# DOut.net
KiCad netlist of a schematic drawn in Altium Designer
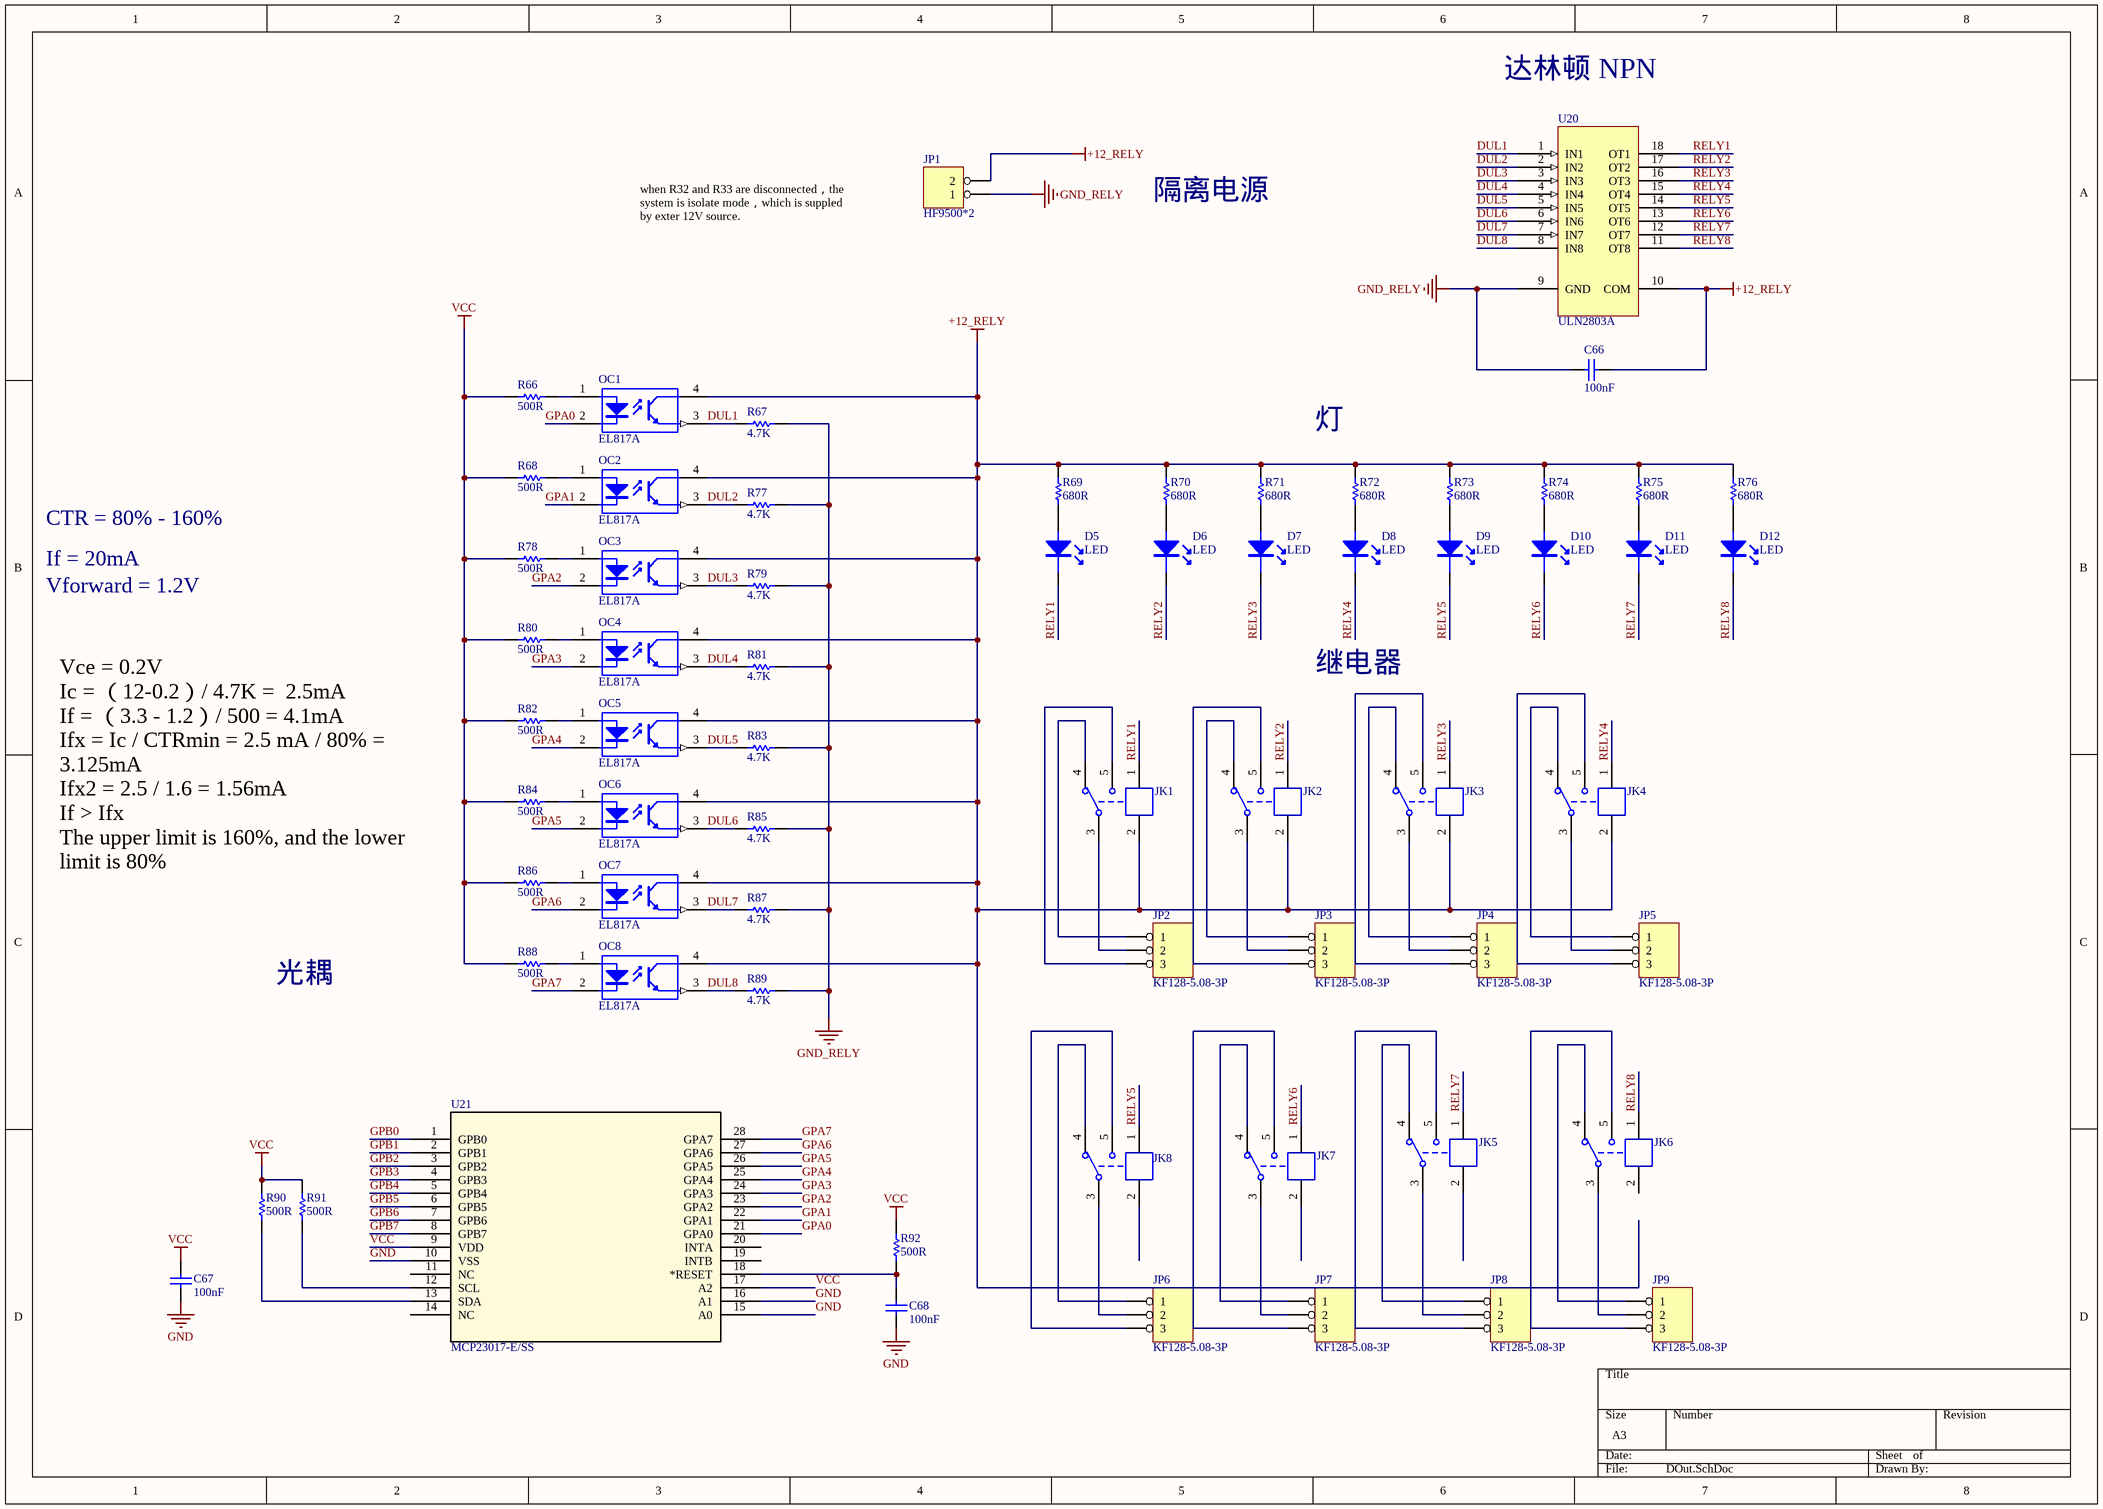
[diagram p0: DOut.SchDoc]

(export (version "E")
  (design (tool "Eeschema 10.0.6"))
  (components
    (comp (ref "C66")
      (value "100nF")
      (footprint "0603C")
      (description "Capacitor")
      (fields (field (name "PUBLISHER") "Altium Limited"))
      (libsource (lib "LJTV1.0") (part "CAP"))
    )
    (comp (ref "C67")
      (value "100nF")
      (footprint "0603C")
      (description "Capacitor")
      (fields (field (name "PUBLISHER") "Altium Limited"))
      (libsource (lib "WarShip_ExtraBoard") (part "CAP"))
    )
    (comp (ref "C68")
      (value "100nF")
      (footprint "0603C")
      (description "Capacitor")
      (fields (field (name "PUBLISHER") "Altium Limited"))
      (libsource (lib "WarShip_ExtraBoard") (part "CAP"))
    )
    (comp (ref "D5")
      (value "LED")
      (footprint "LED-0603G")
      (description "LED 发光二极管")
      (libsource (lib "LJTV1.0") (part "LED"))
    )
    (comp (ref "D6")
      (value "LED")
      (footprint "LED-0603G")
      (description "LED 发光二极管")
      (libsource (lib "LJTV1.0") (part "LED"))
    )
    (comp (ref "D7")
      (value "LED")
      (footprint "LED-0603G")
      (description "LED 发光二极管")
      (libsource (lib "LJTV1.0") (part "LED"))
    )
    (comp (ref "D8")
      (value "LED")
      (footprint "LED-0603G")
      (description "LED 发光二极管")
      (libsource (lib "LJTV1.0") (part "LED"))
    )
    (comp (ref "D9")
      (value "LED")
      (footprint "LED-0603G")
      (description "LED 发光二极管")
      (libsource (lib "LJTV1.0") (part "LED"))
    )
    (comp (ref "D10")
      (value "LED")
      (footprint "LED-0603G")
      (description "LED 发光二极管")
      (libsource (lib "LJTV1.0") (part "LED"))
    )
    (comp (ref "D11")
      (value "LED")
      (footprint "LED-0603G")
      (description "LED 发光二极管")
      (libsource (lib "LJTV1.0") (part "LED"))
    )
    (comp (ref "D12")
      (value "LED")
      (footprint "LED-0603G")
      (description "LED 发光二极管")
      (libsource (lib "LJTV1.0") (part "LED"))
    )
    (comp (ref "JK1")
      (value "SRD-05VDC-SL-C")
      (footprint "SRD-C_B")
      (description "5V一组转换")
      (libsource (lib "LJTV1.0") (part "SRD-05VDC-SL-C"))
    )
    (comp (ref "JK2")
      (value "SRD-05VDC-SL-C")
      (footprint "SRD-C_B")
      (description "5V一组转换")
      (libsource (lib "LJTV1.0") (part "SRD-05VDC-SL-C"))
    )
    (comp (ref "JK3")
      (value "SRD-05VDC-SL-C")
      (footprint "SRD-C_B")
      (description "5V一组转换")
      (libsource (lib "LJTV1.0") (part "SRD-05VDC-SL-C"))
    )
    (comp (ref "JK4")
      (value "SRD-05VDC-SL-C")
      (footprint "SRD-C_B")
      (description "5V一组转换")
      (libsource (lib "LJTV1.0") (part "SRD-05VDC-SL-C"))
    )
    (comp (ref "JK5")
      (value "SRD-05VDC-SL-C")
      (footprint "SRD-C_B")
      (description "5V一组转换")
      (libsource (lib "LJTV1.0") (part "SRD-05VDC-SL-C"))
    )
    (comp (ref "JK6")
      (value "SRD-05VDC-SL-C")
      (footprint "SRD-C_B")
      (description "5V一组转换")
      (libsource (lib "LJTV1.0") (part "SRD-05VDC-SL-C"))
    )
    (comp (ref "JK7")
      (value "SRD-05VDC-SL-C")
      (footprint "SRD-C_B")
      (description "5V一组转换")
      (libsource (lib "LJTV1.0") (part "SRD-05VDC-SL-C"))
    )
    (comp (ref "JK8")
      (value "SRD-05VDC-SL-C")
      (footprint "SRD-C_B")
      (description "5V一组转换")
      (libsource (lib "LJTV1.0") (part "SRD-05VDC-SL-C"))
    )
    (comp (ref "JP1")
      (value "HF9500*2")
      (footprint "KF128-5.08-2P")
      (libsource (lib "LJTV1.0") (part "HEADER 2"))
    )
    (comp (ref "JP2")
      (value "KF128-5.08-3P")
      (footprint "KF128-5.08-3P")
      (libsource (lib "LJTV1.0") (part "HEADER 3"))
    )
    (comp (ref "JP3")
      (value "KF128-5.08-3P")
      (footprint "KF128-5.08-3P")
      (libsource (lib "LJTV1.0") (part "HEADER 3"))
    )
    (comp (ref "JP4")
      (value "KF128-5.08-3P")
      (footprint "KF128-5.08-3P")
      (libsource (lib "LJTV1.0") (part "HEADER 3"))
    )
    (comp (ref "JP5")
      (value "KF128-5.08-3P")
      (footprint "KF128-5.08-3P")
      (libsource (lib "LJTV1.0") (part "HEADER 3"))
    )
    (comp (ref "JP6")
      (value "KF128-5.08-3P")
      (footprint "KF128-5.08-3P")
      (libsource (lib "LJTV1.0") (part "HEADER 3"))
    )
    (comp (ref "JP7")
      (value "KF128-5.08-3P")
      (footprint "KF128-5.08-3P")
      (libsource (lib "LJTV1.0") (part "HEADER 3"))
    )
    (comp (ref "JP8")
      (value "KF128-5.08-3P")
      (footprint "KF128-5.08-3P")
      (libsource (lib "LJTV1.0") (part "HEADER 3"))
    )
    (comp (ref "JP9")
      (value "KF128-5.08-3P")
      (footprint "KF128-5.08-3P")
      (libsource (lib "LJTV1.0") (part "HEADER 3"))
    )
    (comp (ref "OC1")
      (value "EL817A")
      (footprint "SMD_PC817")
      (description "线性光耦")
      (libsource (lib "LJTV1.0") (part "EL357N"))
    )
    (comp (ref "OC2")
      (value "EL817A")
      (footprint "SMD_PC817")
      (description "线性光耦")
      (libsource (lib "LJTV1.0") (part "EL357N"))
    )
    (comp (ref "OC3")
      (value "EL817A")
      (footprint "SMD_PC817")
      (description "线性光耦")
      (libsource (lib "LJTV1.0") (part "EL357N"))
    )
    (comp (ref "OC4")
      (value "EL817A")
      (footprint "SMD_PC817")
      (description "线性光耦")
      (libsource (lib "LJTV1.0") (part "EL357N"))
    )
    (comp (ref "OC5")
      (value "EL817A")
      (footprint "SMD_PC817")
      (description "线性光耦")
      (libsource (lib "LJTV1.0") (part "EL357N"))
    )
    (comp (ref "OC6")
      (value "EL817A")
      (footprint "SMD_PC817")
      (description "线性光耦")
      (libsource (lib "LJTV1.0") (part "EL357N"))
    )
    (comp (ref "OC7")
      (value "EL817A")
      (footprint "SMD_PC817")
      (description "线性光耦")
      (libsource (lib "LJTV1.0") (part "EL357N"))
    )
    (comp (ref "OC8")
      (value "EL817A")
      (footprint "SMD_PC817")
      (description "线性光耦")
      (libsource (lib "LJTV1.0") (part "EL357N"))
    )
    (comp (ref "R66")
      (value "500R")
      (footprint "0805R")
      (description "Resistor")
      (fields (field (name "PUBLISHER") "Altium Limited"))
      (libsource (lib "LJTV1.0") (part "RES"))
    )
    (comp (ref "R67")
      (value "4.7K")
      (footprint "0603R")
      (description "Resistor")
      (fields (field (name "PUBLISHER") "Altium Limited"))
      (libsource (lib "LJTV1.0") (part "RES"))
    )
    (comp (ref "R68")
      (value "500R")
      (footprint "0805R")
      (description "Resistor")
      (fields (field (name "PUBLISHER") "Altium Limited"))
      (libsource (lib "LJTV1.0") (part "RES"))
    )
    (comp (ref "R69")
      (value "680R")
      (footprint "0805R")
      (description "Resistor")
      (fields (field (name "PUBLISHER") "Altium Limited"))
      (libsource (lib "LJTV1.0") (part "RES"))
    )
    (comp (ref "R70")
      (value "680R")
      (footprint "0805R")
      (description "Resistor")
      (fields (field (name "PUBLISHER") "Altium Limited"))
      (libsource (lib "LJTV1.0") (part "RES"))
    )
    (comp (ref "R71")
      (value "680R")
      (footprint "0805R")
      (description "Resistor")
      (fields (field (name "PUBLISHER") "Altium Limited"))
      (libsource (lib "LJTV1.0") (part "RES"))
    )
    (comp (ref "R72")
      (value "680R")
      (footprint "0805R")
      (description "Resistor")
      (fields (field (name "PUBLISHER") "Altium Limited"))
      (libsource (lib "LJTV1.0") (part "RES"))
    )
    (comp (ref "R73")
      (value "680R")
      (footprint "0805R")
      (description "Resistor")
      (fields (field (name "PUBLISHER") "Altium Limited"))
      (libsource (lib "LJTV1.0") (part "RES"))
    )
    (comp (ref "R74")
      (value "680R")
      (footprint "0805R")
      (description "Resistor")
      (fields (field (name "PUBLISHER") "Altium Limited"))
      (libsource (lib "LJTV1.0") (part "RES"))
    )
    (comp (ref "R75")
      (value "680R")
      (footprint "0805R")
      (description "Resistor")
      (fields (field (name "PUBLISHER") "Altium Limited"))
      (libsource (lib "LJTV1.0") (part "RES"))
    )
    (comp (ref "R76")
      (value "680R")
      (footprint "0805R")
      (description "Resistor")
      (fields (field (name "PUBLISHER") "Altium Limited"))
      (libsource (lib "LJTV1.0") (part "RES"))
    )
    (comp (ref "R77")
      (value "4.7K")
      (footprint "0603R")
      (description "Resistor")
      (fields (field (name "PUBLISHER") "Altium Limited"))
      (libsource (lib "LJTV1.0") (part "RES"))
    )
    (comp (ref "R78")
      (value "500R")
      (footprint "0805R")
      (description "Resistor")
      (fields (field (name "PUBLISHER") "Altium Limited"))
      (libsource (lib "LJTV1.0") (part "RES"))
    )
    (comp (ref "R79")
      (value "4.7K")
      (footprint "0603R")
      (description "Resistor")
      (fields (field (name "PUBLISHER") "Altium Limited"))
      (libsource (lib "LJTV1.0") (part "RES"))
    )
    (comp (ref "R80")
      (value "500R")
      (footprint "0805R")
      (description "Resistor")
      (fields (field (name "PUBLISHER") "Altium Limited"))
      (libsource (lib "LJTV1.0") (part "RES"))
    )
    (comp (ref "R81")
      (value "4.7K")
      (footprint "0603R")
      (description "Resistor")
      (fields (field (name "PUBLISHER") "Altium Limited"))
      (libsource (lib "LJTV1.0") (part "RES"))
    )
    (comp (ref "R82")
      (value "500R")
      (footprint "0805R")
      (description "Resistor")
      (fields (field (name "PUBLISHER") "Altium Limited"))
      (libsource (lib "LJTV1.0") (part "RES"))
    )
    (comp (ref "R83")
      (value "4.7K")
      (footprint "0603R")
      (description "Resistor")
      (fields (field (name "PUBLISHER") "Altium Limited"))
      (libsource (lib "LJTV1.0") (part "RES"))
    )
    (comp (ref "R84")
      (value "500R")
      (footprint "0805R")
      (description "Resistor")
      (fields (field (name "PUBLISHER") "Altium Limited"))
      (libsource (lib "LJTV1.0") (part "RES"))
    )
    (comp (ref "R85")
      (value "4.7K")
      (footprint "0603R")
      (description "Resistor")
      (fields (field (name "PUBLISHER") "Altium Limited"))
      (libsource (lib "LJTV1.0") (part "RES"))
    )
    (comp (ref "R86")
      (value "500R")
      (footprint "0805R")
      (description "Resistor")
      (fields (field (name "PUBLISHER") "Altium Limited"))
      (libsource (lib "LJTV1.0") (part "RES"))
    )
    (comp (ref "R87")
      (value "4.7K")
      (footprint "0603R")
      (description "Resistor")
      (fields (field (name "PUBLISHER") "Altium Limited"))
      (libsource (lib "LJTV1.0") (part "RES"))
    )
    (comp (ref "R88")
      (value "500R")
      (footprint "0805R")
      (description "Resistor")
      (fields (field (name "PUBLISHER") "Altium Limited"))
      (libsource (lib "LJTV1.0") (part "RES"))
    )
    (comp (ref "R89")
      (value "4.7K")
      (footprint "0603R")
      (description "Resistor")
      (fields (field (name "PUBLISHER") "Altium Limited"))
      (libsource (lib "LJTV1.0") (part "RES"))
    )
    (comp (ref "R90")
      (value "500R")
      (footprint "0805R")
      (description "Resistor")
      (fields (field (name "PUBLISHER") "Altium Limited"))
      (libsource (lib "WarShip_ExtraBoard") (part "RES"))
    )
    (comp (ref "R91")
      (value "500R")
      (footprint "0805R")
      (description "Resistor")
      (fields (field (name "PUBLISHER") "Altium Limited"))
      (libsource (lib "WarShip_ExtraBoard") (part "RES"))
    )
    (comp (ref "R92")
      (value "500R")
      (footprint "0805R")
      (description "Resistor")
      (fields (field (name "PUBLISHER") "Altium Limited"))
      (libsource (lib "WarShip_ExtraBoard") (part "RES"))
    )
    (comp (ref "U20")
      (value "ULN2803A")
      (footprint "SOP18 - 300mil")
      (description "8 channels Darlington")
      (libsource (lib "LJTV1.0") (part "ULN2803A"))
    )
    (comp (ref "U21")
      (value "MCP23017-E/SS")
      (footprint "SSOP28_MC_MCH")
      (description "No Description Available")
      (fields (field (name "COPYRIGHT") "Copyright (C) 2021 Ultra Librarian. All rights reserved."))
      (libsource (lib "MCP23017-E&slash_SS") (part "MCP23017-E/SS"))
    )
  )
  (nets
    (net (code "1") (name "+12_RELY") (class "Default")
      (node (ref "C66") (pin "2") (pinfunction "2_2") (pintype "passive"))
      (node (ref "JK1") (pin "2") (pinfunction "2_2") (pintype "passive"))
      (node (ref "JK2") (pin "2") (pinfunction "2_2") (pintype "passive"))
      (node (ref "JK3") (pin "2") (pinfunction "2_2") (pintype "passive"))
      (node (ref "JK4") (pin "2") (pinfunction "2_2") (pintype "passive"))
      (node (ref "JP1") (pin "2") (pinfunction "2_2") (pintype "passive"))
      (node (ref "OC1") (pin "4") (pinfunction "C_4") (pintype "passive"))
      (node (ref "OC2") (pin "4") (pinfunction "C_4") (pintype "passive"))
      (node (ref "OC3") (pin "4") (pinfunction "C_4") (pintype "passive"))
      (node (ref "OC4") (pin "4") (pinfunction "C_4") (pintype "passive"))
      (node (ref "OC5") (pin "4") (pinfunction "C_4") (pintype "passive"))
      (node (ref "OC6") (pin "4") (pinfunction "C_4") (pintype "passive"))
      (node (ref "OC7") (pin "4") (pinfunction "C_4") (pintype "passive"))
      (node (ref "OC8") (pin "4") (pinfunction "C_4") (pintype "passive"))
      (node (ref "R69") (pin "1") (pinfunction "1_1") (pintype "passive"))
      (node (ref "R70") (pin "1") (pinfunction "1_1") (pintype "passive"))
      (node (ref "R71") (pin "1") (pinfunction "1_1") (pintype "passive"))
      (node (ref "R72") (pin "1") (pinfunction "1_1") (pintype "passive"))
      (node (ref "R73") (pin "1") (pinfunction "1_1") (pintype "passive"))
      (node (ref "R74") (pin "1") (pinfunction "1_1") (pintype "passive"))
      (node (ref "R75") (pin "1") (pinfunction "1_1") (pintype "passive"))
      (node (ref "R76") (pin "1") (pinfunction "1_1") (pintype "passive"))
      (node (ref "U20") (pin "10") (pinfunction "COM_10") (pintype "power_in"))
    )
    (net (code "2") (name "/DUL1") (class "Default")
      (node (ref "OC1") (pin "3") (pinfunction "E_3") (pintype "output"))
      (node (ref "R67") (pin "1") (pinfunction "1_1") (pintype "passive"))
      (node (ref "U20") (pin "1") (pinfunction "IN1_1") (pintype "input"))
    )
    (net (code "3") (name "/DUL2") (class "Default")
      (node (ref "OC2") (pin "3") (pinfunction "E_3") (pintype "output"))
      (node (ref "R77") (pin "1") (pinfunction "1_1") (pintype "passive"))
      (node (ref "U20") (pin "2") (pinfunction "IN2_2") (pintype "input"))
    )
    (net (code "4") (name "/DUL3") (class "Default")
      (node (ref "OC3") (pin "3") (pinfunction "E_3") (pintype "output"))
      (node (ref "R79") (pin "1") (pinfunction "1_1") (pintype "passive"))
      (node (ref "U20") (pin "3") (pinfunction "IN3_3") (pintype "input"))
    )
    (net (code "5") (name "/DUL4") (class "Default")
      (node (ref "OC4") (pin "3") (pinfunction "E_3") (pintype "output"))
      (node (ref "R81") (pin "1") (pinfunction "1_1") (pintype "passive"))
      (node (ref "U20") (pin "4") (pinfunction "IN4_4") (pintype "input"))
    )
    (net (code "6") (name "/DUL5") (class "Default")
      (node (ref "OC5") (pin "3") (pinfunction "E_3") (pintype "output"))
      (node (ref "R83") (pin "1") (pinfunction "1_1") (pintype "passive"))
      (node (ref "U20") (pin "5") (pinfunction "IN5_5") (pintype "input"))
    )
    (net (code "7") (name "/DUL6") (class "Default")
      (node (ref "OC6") (pin "3") (pinfunction "E_3") (pintype "output"))
      (node (ref "R85") (pin "1") (pinfunction "1_1") (pintype "passive"))
      (node (ref "U20") (pin "6") (pinfunction "IN6_6") (pintype "input"))
    )
    (net (code "8") (name "/DUL7") (class "Default")
      (node (ref "OC7") (pin "3") (pinfunction "E_3") (pintype "output"))
      (node (ref "R87") (pin "1") (pinfunction "1_1") (pintype "passive"))
      (node (ref "U20") (pin "7") (pinfunction "IN7_7") (pintype "input"))
    )
    (net (code "9") (name "/DUL8") (class "Default")
      (node (ref "OC8") (pin "3") (pinfunction "E_3") (pintype "output"))
      (node (ref "R89") (pin "1") (pinfunction "1_1") (pintype "passive"))
      (node (ref "U20") (pin "8") (pinfunction "IN8_8") (pintype "passive"))
    )
    (net (code "10") (name "/GPA0") (class "Default")
      (node (ref "OC1") (pin "2") (pinfunction "K_2") (pintype "passive"))
      (node (ref "U21") (pin "21") (pinfunction "GPA0_21") (pintype "passive"))
    )
    (net (code "11") (name "/GPA1") (class "Default")
      (node (ref "OC2") (pin "2") (pinfunction "K_2") (pintype "passive"))
      (node (ref "U21") (pin "22") (pinfunction "GPA1_22") (pintype "passive"))
    )
    (net (code "12") (name "/GPA2") (class "Default")
      (node (ref "OC3") (pin "2") (pinfunction "K_2") (pintype "passive"))
      (node (ref "U21") (pin "23") (pinfunction "GPA2_23") (pintype "passive"))
    )
    (net (code "13") (name "/GPA3") (class "Default")
      (node (ref "OC4") (pin "2") (pinfunction "K_2") (pintype "passive"))
      (node (ref "U21") (pin "24") (pinfunction "GPA3_24") (pintype "passive"))
    )
    (net (code "14") (name "/GPA4") (class "Default")
      (node (ref "OC5") (pin "2") (pinfunction "K_2") (pintype "passive"))
      (node (ref "U21") (pin "25") (pinfunction "GPA4_25") (pintype "passive"))
    )
    (net (code "15") (name "/GPA5") (class "Default")
      (node (ref "OC6") (pin "2") (pinfunction "K_2") (pintype "passive"))
      (node (ref "U21") (pin "26") (pinfunction "GPA5_26") (pintype "passive"))
    )
    (net (code "16") (name "/GPA6") (class "Default")
      (node (ref "OC7") (pin "2") (pinfunction "K_2") (pintype "passive"))
      (node (ref "U21") (pin "27") (pinfunction "GPA6_27") (pintype "passive"))
    )
    (net (code "17") (name "/GPA7") (class "Default")
      (node (ref "OC8") (pin "2") (pinfunction "K_2") (pintype "passive"))
      (node (ref "U21") (pin "28") (pinfunction "GPA7_28") (pintype "passive"))
    )
    (net (code "18") (name "/GPB0") (class "Default")
      (node (ref "U21") (pin "1") (pinfunction "GPB0_1") (pintype "passive"))
    )
    (net (code "19") (name "/GPB1") (class "Default")
      (node (ref "U21") (pin "2") (pinfunction "GPB1_2") (pintype "passive"))
    )
    (net (code "20") (name "/GPB2") (class "Default")
      (node (ref "U21") (pin "3") (pinfunction "GPB2_3") (pintype "passive"))
    )
    (net (code "21") (name "/GPB3") (class "Default")
      (node (ref "U21") (pin "4") (pinfunction "GPB3_4") (pintype "passive"))
    )
    (net (code "22") (name "/GPB4") (class "Default")
      (node (ref "U21") (pin "5") (pinfunction "GPB4_5") (pintype "passive"))
    )
    (net (code "23") (name "/GPB5") (class "Default")
      (node (ref "U21") (pin "6") (pinfunction "GPB5_6") (pintype "passive"))
    )
    (net (code "24") (name "/GPB6") (class "Default")
      (node (ref "U21") (pin "7") (pinfunction "GPB6_7") (pintype "passive"))
    )
    (net (code "25") (name "/GPB7") (class "Default")
      (node (ref "U21") (pin "8") (pinfunction "GPB7_8") (pintype "passive"))
    )
    (net (code "26") (name "/RELY1") (class "Default")
      (node (ref "D5") (pin "2") (pinfunction "K_2") (pintype "passive"))
      (node (ref "JK1") (pin "1") (pinfunction "1_1") (pintype "passive"))
      (node (ref "U20") (pin "18") (pinfunction "OT1_18") (pintype "passive"))
    )
    (net (code "27") (name "/RELY2") (class "Default")
      (node (ref "D6") (pin "2") (pinfunction "K_2") (pintype "passive"))
      (node (ref "JK2") (pin "1") (pinfunction "1_1") (pintype "passive"))
      (node (ref "U20") (pin "17") (pinfunction "OT2_17") (pintype "passive"))
    )
    (net (code "28") (name "/RELY3") (class "Default")
      (node (ref "D7") (pin "2") (pinfunction "K_2") (pintype "passive"))
      (node (ref "JK3") (pin "1") (pinfunction "1_1") (pintype "passive"))
      (node (ref "U20") (pin "16") (pinfunction "OT3_16") (pintype "passive"))
    )
    (net (code "29") (name "/RELY4") (class "Default")
      (node (ref "D8") (pin "2") (pinfunction "K_2") (pintype "passive"))
      (node (ref "JK4") (pin "1") (pinfunction "1_1") (pintype "passive"))
      (node (ref "U20") (pin "15") (pinfunction "OT4_15") (pintype "passive"))
    )
    (net (code "30") (name "/RELY5") (class "Default")
      (node (ref "D9") (pin "2") (pinfunction "K_2") (pintype "passive"))
      (node (ref "JK8") (pin "1") (pinfunction "1_1") (pintype "passive"))
      (node (ref "U20") (pin "14") (pinfunction "OT5_14") (pintype "passive"))
    )
    (net (code "31") (name "/RELY6") (class "Default")
      (node (ref "D10") (pin "2") (pinfunction "K_2") (pintype "passive"))
      (node (ref "JK7") (pin "1") (pinfunction "1_1") (pintype "passive"))
      (node (ref "U20") (pin "13") (pinfunction "OT6_13") (pintype "passive"))
    )
    (net (code "32") (name "/RELY7") (class "Default")
      (node (ref "D11") (pin "2") (pinfunction "K_2") (pintype "passive"))
      (node (ref "JK5") (pin "1") (pinfunction "1_1") (pintype "passive"))
      (node (ref "U20") (pin "12") (pinfunction "OT7_12") (pintype "passive"))
    )
    (net (code "33") (name "/RELY8") (class "Default")
      (node (ref "D12") (pin "2") (pinfunction "K_2") (pintype "passive"))
      (node (ref "JK6") (pin "1") (pinfunction "1_1") (pintype "passive"))
      (node (ref "U20") (pin "11") (pinfunction "OT8_11") (pintype "passive"))
    )
    (net (code "34") (name "GND") (class "Default")
      (node (ref "C67") (pin "1") (pinfunction "1_1") (pintype "passive"))
      (node (ref "C68") (pin "1") (pinfunction "1_1") (pintype "passive"))
      (node (ref "U21") (pin "10") (pinfunction "VSS_10") (pintype "passive"))
      (node (ref "U21") (pin "15") (pinfunction "A0_15") (pintype "passive"))
      (node (ref "U21") (pin "16") (pinfunction "A1_16") (pintype "passive"))
    )
    (net (code "35") (name "GND_RELY") (class "Default")
      (node (ref "C66") (pin "1") (pinfunction "1_1") (pintype "passive"))
      (node (ref "JP1") (pin "1") (pinfunction "1_1") (pintype "passive"))
      (node (ref "R67") (pin "2") (pinfunction "2_2") (pintype "passive"))
      (node (ref "R77") (pin "2") (pinfunction "2_2") (pintype "passive"))
      (node (ref "R79") (pin "2") (pinfunction "2_2") (pintype "passive"))
      (node (ref "R81") (pin "2") (pinfunction "2_2") (pintype "passive"))
      (node (ref "R83") (pin "2") (pinfunction "2_2") (pintype "passive"))
      (node (ref "R85") (pin "2") (pinfunction "2_2") (pintype "passive"))
      (node (ref "R87") (pin "2") (pinfunction "2_2") (pintype "passive"))
      (node (ref "R89") (pin "2") (pinfunction "2_2") (pintype "passive"))
      (node (ref "U20") (pin "9") (pinfunction "GND_9") (pintype "power_in"))
    )
    (net (code "36") (name "Net-(D5-A)") (class "Default")
      (node (ref "D5") (pin "1") (pinfunction "A_1") (pintype "passive"))
      (node (ref "R69") (pin "2") (pinfunction "2_2") (pintype "passive"))
    )
    (net (code "37") (name "Net-(D6-A)") (class "Default")
      (node (ref "D6") (pin "1") (pinfunction "A_1") (pintype "passive"))
      (node (ref "R70") (pin "2") (pinfunction "2_2") (pintype "passive"))
    )
    (net (code "38") (name "Net-(D7-A)") (class "Default")
      (node (ref "D7") (pin "1") (pinfunction "A_1") (pintype "passive"))
      (node (ref "R71") (pin "2") (pinfunction "2_2") (pintype "passive"))
    )
    (net (code "39") (name "Net-(D8-A)") (class "Default")
      (node (ref "D8") (pin "1") (pinfunction "A_1") (pintype "passive"))
      (node (ref "R72") (pin "2") (pinfunction "2_2") (pintype "passive"))
    )
    (net (code "40") (name "Net-(D9-A)") (class "Default")
      (node (ref "D9") (pin "1") (pinfunction "A_1") (pintype "passive"))
      (node (ref "R73") (pin "2") (pinfunction "2_2") (pintype "passive"))
    )
    (net (code "41") (name "Net-(D10-A)") (class "Default")
      (node (ref "D10") (pin "1") (pinfunction "A_1") (pintype "passive"))
      (node (ref "R74") (pin "2") (pinfunction "2_2") (pintype "passive"))
    )
    (net (code "42") (name "Net-(D11-A)") (class "Default")
      (node (ref "D11") (pin "1") (pinfunction "A_1") (pintype "passive"))
      (node (ref "R75") (pin "2") (pinfunction "2_2") (pintype "passive"))
    )
    (net (code "43") (name "Net-(D12-A)") (class "Default")
      (node (ref "D12") (pin "1") (pinfunction "A_1") (pintype "passive"))
      (node (ref "R76") (pin "2") (pinfunction "2_2") (pintype "passive"))
    )
    (net (code "44") (name "Net-(JK1-Pad3)") (class "Default")
      (node (ref "JK1") (pin "3") (pinfunction "3_3") (pintype "passive"))
      (node (ref "JP2") (pin "2") (pinfunction "2_2") (pintype "passive"))
    )
    (net (code "45") (name "Net-(JK1-Pad4)") (class "Default")
      (node (ref "JK1") (pin "4") (pinfunction "4_4") (pintype "passive"))
      (node (ref "JP2") (pin "1") (pinfunction "1_1") (pintype "passive"))
    )
    (net (code "46") (name "Net-(JK1-Pad5)") (class "Default")
      (node (ref "JK1") (pin "5") (pinfunction "5_5") (pintype "passive"))
      (node (ref "JP2") (pin "3") (pinfunction "3_3") (pintype "passive"))
    )
    (net (code "47") (name "Net-(JK2-Pad3)") (class "Default")
      (node (ref "JK2") (pin "3") (pinfunction "3_3") (pintype "passive"))
      (node (ref "JP3") (pin "2") (pinfunction "2_2") (pintype "passive"))
    )
    (net (code "48") (name "Net-(JK2-Pad4)") (class "Default")
      (node (ref "JK2") (pin "4") (pinfunction "4_4") (pintype "passive"))
      (node (ref "JP3") (pin "1") (pinfunction "1_1") (pintype "passive"))
    )
    (net (code "49") (name "Net-(JK2-Pad5)") (class "Default")
      (node (ref "JK2") (pin "5") (pinfunction "5_5") (pintype "passive"))
      (node (ref "JP3") (pin "3") (pinfunction "3_3") (pintype "passive"))
    )
    (net (code "50") (name "Net-(JK3-Pad3)") (class "Default")
      (node (ref "JK3") (pin "3") (pinfunction "3_3") (pintype "passive"))
      (node (ref "JP4") (pin "2") (pinfunction "2_2") (pintype "passive"))
    )
    (net (code "51") (name "Net-(JK3-Pad4)") (class "Default")
      (node (ref "JK3") (pin "4") (pinfunction "4_4") (pintype "passive"))
      (node (ref "JP4") (pin "1") (pinfunction "1_1") (pintype "passive"))
    )
    (net (code "52") (name "Net-(JK3-Pad5)") (class "Default")
      (node (ref "JK3") (pin "5") (pinfunction "5_5") (pintype "passive"))
      (node (ref "JP4") (pin "3") (pinfunction "3_3") (pintype "passive"))
    )
    (net (code "53") (name "Net-(JK4-Pad3)") (class "Default")
      (node (ref "JK4") (pin "3") (pinfunction "3_3") (pintype "passive"))
      (node (ref "JP5") (pin "2") (pinfunction "2_2") (pintype "passive"))
    )
    (net (code "54") (name "Net-(JK4-Pad4)") (class "Default")
      (node (ref "JK4") (pin "4") (pinfunction "4_4") (pintype "passive"))
      (node (ref "JP5") (pin "1") (pinfunction "1_1") (pintype "passive"))
    )
    (net (code "55") (name "Net-(JK4-Pad5)") (class "Default")
      (node (ref "JK4") (pin "5") (pinfunction "5_5") (pintype "passive"))
      (node (ref "JP5") (pin "3") (pinfunction "3_3") (pintype "passive"))
    )
    (net (code "56") (name "Net-(JK5-Pad3)") (class "Default")
      (node (ref "JK5") (pin "3") (pinfunction "3_3") (pintype "passive"))
      (node (ref "JP8") (pin "2") (pinfunction "2_2") (pintype "passive"))
    )
    (net (code "57") (name "Net-(JK5-Pad4)") (class "Default")
      (node (ref "JK5") (pin "4") (pinfunction "4_4") (pintype "passive"))
      (node (ref "JP8") (pin "1") (pinfunction "1_1") (pintype "passive"))
    )
    (net (code "58") (name "Net-(JK5-Pad5)") (class "Default")
      (node (ref "JK5") (pin "5") (pinfunction "5_5") (pintype "passive"))
      (node (ref "JP8") (pin "3") (pinfunction "3_3") (pintype "passive"))
    )
    (net (code "59") (name "Net-(JK6-Pad3)") (class "Default")
      (node (ref "JK6") (pin "3") (pinfunction "3_3") (pintype "passive"))
      (node (ref "JP9") (pin "2") (pinfunction "2_2") (pintype "passive"))
    )
    (net (code "60") (name "Net-(JK6-Pad4)") (class "Default")
      (node (ref "JK6") (pin "4") (pinfunction "4_4") (pintype "passive"))
      (node (ref "JP9") (pin "1") (pinfunction "1_1") (pintype "passive"))
    )
    (net (code "61") (name "Net-(JK6-Pad5)") (class "Default")
      (node (ref "JK6") (pin "5") (pinfunction "5_5") (pintype "passive"))
      (node (ref "JP9") (pin "3") (pinfunction "3_3") (pintype "passive"))
    )
    (net (code "62") (name "Net-(JK7-Pad3)") (class "Default")
      (node (ref "JK7") (pin "3") (pinfunction "3_3") (pintype "passive"))
      (node (ref "JP7") (pin "2") (pinfunction "2_2") (pintype "passive"))
    )
    (net (code "63") (name "Net-(JK7-Pad4)") (class "Default")
      (node (ref "JK7") (pin "4") (pinfunction "4_4") (pintype "passive"))
      (node (ref "JP7") (pin "1") (pinfunction "1_1") (pintype "passive"))
    )
    (net (code "64") (name "Net-(JK7-Pad5)") (class "Default")
      (node (ref "JK7") (pin "5") (pinfunction "5_5") (pintype "passive"))
      (node (ref "JP7") (pin "3") (pinfunction "3_3") (pintype "passive"))
    )
    (net (code "65") (name "Net-(JK8-Pad3)") (class "Default")
      (node (ref "JK8") (pin "3") (pinfunction "3_3") (pintype "passive"))
      (node (ref "JP6") (pin "2") (pinfunction "2_2") (pintype "passive"))
    )
    (net (code "66") (name "Net-(JK8-Pad4)") (class "Default")
      (node (ref "JK8") (pin "4") (pinfunction "4_4") (pintype "passive"))
      (node (ref "JP6") (pin "1") (pinfunction "1_1") (pintype "passive"))
    )
    (net (code "67") (name "Net-(JK8-Pad5)") (class "Default")
      (node (ref "JK8") (pin "5") (pinfunction "5_5") (pintype "passive"))
      (node (ref "JP6") (pin "3") (pinfunction "3_3") (pintype "passive"))
    )
    (net (code "68") (name "Net-(OC1-A)") (class "Default")
      (node (ref "OC1") (pin "1") (pinfunction "A_1") (pintype "passive"))
      (node (ref "R66") (pin "1") (pinfunction "1_1") (pintype "passive"))
    )
    (net (code "69") (name "Net-(OC2-A)") (class "Default")
      (node (ref "OC2") (pin "1") (pinfunction "A_1") (pintype "passive"))
      (node (ref "R68") (pin "1") (pinfunction "1_1") (pintype "passive"))
    )
    (net (code "70") (name "Net-(OC3-A)") (class "Default")
      (node (ref "OC3") (pin "1") (pinfunction "A_1") (pintype "passive"))
      (node (ref "R78") (pin "1") (pinfunction "1_1") (pintype "passive"))
    )
    (net (code "71") (name "Net-(OC4-A)") (class "Default")
      (node (ref "OC4") (pin "1") (pinfunction "A_1") (pintype "passive"))
      (node (ref "R80") (pin "1") (pinfunction "1_1") (pintype "passive"))
    )
    (net (code "72") (name "Net-(OC5-A)") (class "Default")
      (node (ref "OC5") (pin "1") (pinfunction "A_1") (pintype "passive"))
      (node (ref "R82") (pin "1") (pinfunction "1_1") (pintype "passive"))
    )
    (net (code "73") (name "Net-(OC6-A)") (class "Default")
      (node (ref "OC6") (pin "1") (pinfunction "A_1") (pintype "passive"))
      (node (ref "R84") (pin "1") (pinfunction "1_1") (pintype "passive"))
    )
    (net (code "74") (name "Net-(OC7-A)") (class "Default")
      (node (ref "OC7") (pin "1") (pinfunction "A_1") (pintype "passive"))
      (node (ref "R86") (pin "1") (pinfunction "1_1") (pintype "passive"))
    )
    (net (code "75") (name "Net-(OC8-A)") (class "Default")
      (node (ref "OC8") (pin "1") (pinfunction "A_1") (pintype "passive"))
      (node (ref "R88") (pin "1") (pinfunction "1_1") (pintype "passive"))
    )
    (net (code "76") (name "Net-(U21-*RESET)") (class "Default")
      (node (ref "C68") (pin "2") (pinfunction "2_2") (pintype "passive"))
      (node (ref "R92") (pin "1") (pinfunction "1_1") (pintype "passive"))
      (node (ref "U21") (pin "18") (pinfunction "*RESET_18") (pintype "passive"))
    )
    (net (code "77") (name "Net-(U21-SCL)") (class "Default")
      (node (ref "R91") (pin "1") (pinfunction "1_1") (pintype "passive"))
      (node (ref "U21") (pin "12") (pinfunction "SCL_12") (pintype "passive"))
    )
    (net (code "78") (name "Net-(U21-SDA)") (class "Default")
      (node (ref "R90") (pin "1") (pinfunction "1_1") (pintype "passive"))
      (node (ref "U21") (pin "13") (pinfunction "SDA_13") (pintype "passive"))
    )
    (net (code "79") (name "VCC") (class "Default")
      (node (ref "C67") (pin "2") (pinfunction "2_2") (pintype "passive"))
      (node (ref "R66") (pin "2") (pinfunction "2_2") (pintype "passive"))
      (node (ref "R68") (pin "2") (pinfunction "2_2") (pintype "passive"))
      (node (ref "R78") (pin "2") (pinfunction "2_2") (pintype "passive"))
      (node (ref "R80") (pin "2") (pinfunction "2_2") (pintype "passive"))
      (node (ref "R82") (pin "2") (pinfunction "2_2") (pintype "passive"))
      (node (ref "R84") (pin "2") (pinfunction "2_2") (pintype "passive"))
      (node (ref "R86") (pin "2") (pinfunction "2_2") (pintype "passive"))
      (node (ref "R88") (pin "2") (pinfunction "2_2") (pintype "passive"))
      (node (ref "R90") (pin "2") (pinfunction "2_2") (pintype "passive"))
      (node (ref "R91") (pin "2") (pinfunction "2_2") (pintype "passive"))
      (node (ref "R92") (pin "2") (pinfunction "2_2") (pintype "passive"))
      (node (ref "U21") (pin "17") (pinfunction "A2_17") (pintype "passive"))
      (node (ref "U21") (pin "9") (pinfunction "VDD_9") (pintype "passive"))
    )
    (net (code "80") (name "unconnected-(JK5-Pad2)") (class "Default")
      (node (ref "JK5") (pin "2") (pinfunction "2_2") (pintype "passive"))
    )
    (net (code "81") (name "unconnected-(JK6-Pad2)") (class "Default")
      (node (ref "JK6") (pin "2") (pinfunction "2_2") (pintype "passive"))
    )
    (net (code "82") (name "unconnected-(JK7-Pad2)") (class "Default")
      (node (ref "JK7") (pin "2") (pinfunction "2_2") (pintype "passive"))
    )
    (net (code "83") (name "unconnected-(JK8-Pad2)") (class "Default")
      (node (ref "JK8") (pin "2") (pinfunction "2_2") (pintype "passive"))
    )
    (net (code "84") (name "unconnected-(U21-INTA-Pad20)") (class "Default")
      (node (ref "U21") (pin "20") (pinfunction "INTA_20") (pintype "passive"))
    )
    (net (code "85") (name "unconnected-(U21-INTB-Pad19)") (class "Default")
      (node (ref "U21") (pin "19") (pinfunction "INTB_19") (pintype "passive"))
    )
    (net (code "86") (name "unconnected-(U21-NC-Pad11)") (class "Default")
      (node (ref "U21") (pin "11") (pinfunction "NC_11") (pintype "passive"))
    )
    (net (code "87") (name "unconnected-(U21-NC-Pad14)") (class "Default")
      (node (ref "U21") (pin "14") (pinfunction "NC_14") (pintype "passive"))
    )
  )
)
